# V1_0.net
KiCad netlist of a schematic drawn in Altium Designer
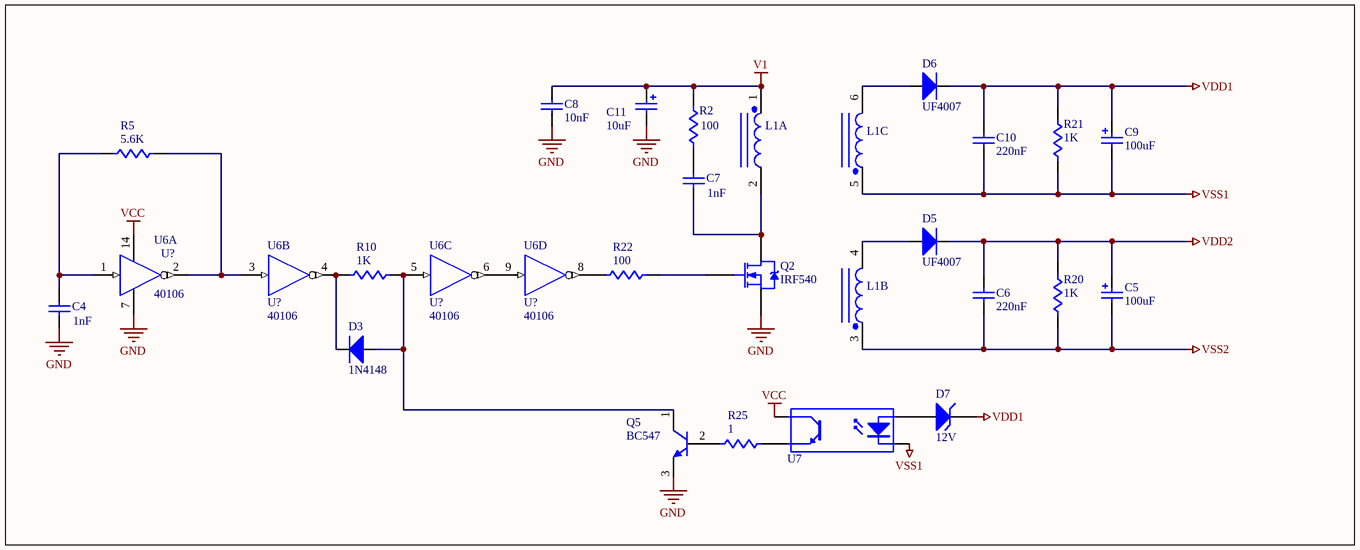
[diagram p0: V1.0.SchDoc]

(export (version "E")
  (design (tool "Eeschema 10.0.6"))
  (components
    (comp (ref "C4")
      (value "1nF")
      (footprint "CAPNTO2.54-3.05x1.78A")
      (description "Capacitor")
      (fields
        (field (name "MANUFACTURER") "Generic Components")
        (field (name "Comment") "Cap")
        (field (name "PUBLISHER") "Altium Limited")
      )
      (libsource (lib "Miscellaneous Devices") (part "Cap"))
    )
    (comp (ref "C5")
      (value "100uF")
      (footprint "CAPPR2.5-6.3x5")
      (description "Polarized Capacitor (Radial)")
      (fields
        (field (name "MANUFACTURER") "Generic Components")
        (field (name "Comment") "Cap Pol1")
        (field (name "PUBLISHER") "Altium Limited")
      )
      (libsource (lib "Miscellaneous Devices") (part "Cap Pol1"))
    )
    (comp (ref "C6")
      (value "220nF")
      (footprint "CAPNTO5.08-7.37x3.94")
      (description "Capacitor")
      (fields
        (field (name "MANUFACTURER") "Generic Components")
        (field (name "Comment") "Cap")
        (field (name "PUBLISHER") "Altium Limited")
      )
      (libsource (lib "Miscellaneous Devices") (part "Cap"))
    )
    (comp (ref "C7")
      (value "1nF")
      (footprint "CAPNTO2.54-3.56x2.03")
      (description "Capacitor")
      (fields
        (field (name "MANUFACTURER") "Generic Components")
        (field (name "Comment") "Cap")
        (field (name "PUBLISHER") "Altium Limited")
      )
      (libsource (lib "Miscellaneous Devices") (part "Cap"))
    )
    (comp (ref "C8")
      (value "10nF")
      (footprint "CAPNTO2.54-3.05x1.78A")
      (description "Capacitor")
      (fields
        (field (name "MANUFACTURER") "Generic Components")
        (field (name "Comment") "Cap")
        (field (name "PUBLISHER") "Altium Limited")
      )
      (libsource (lib "Miscellaneous Devices") (part "Cap"))
    )
    (comp (ref "C9")
      (value "100uF")
      (footprint "CAPPR2.5-6.3x5")
      (description "Polarized Capacitor (Radial)")
      (fields
        (field (name "MANUFACTURER") "Generic Components")
        (field (name "Comment") "Cap Pol1")
        (field (name "PUBLISHER") "Altium Limited")
      )
      (libsource (lib "Miscellaneous Devices") (part "Cap Pol1"))
    )
    (comp (ref "C10")
      (value "220nF")
      (footprint "CAPNTO5.08-7.37x3.94")
      (description "Capacitor")
      (fields
        (field (name "MANUFACTURER") "Generic Components")
        (field (name "Comment") "Cap")
        (field (name "PUBLISHER") "Altium Limited")
      )
      (libsource (lib "Miscellaneous Devices") (part "Cap"))
    )
    (comp (ref "C11")
      (value "10uF")
      (footprint "CAPPR2.5-6.3x5")
      (description "Polarized Capacitor (Radial)")
      (fields
        (field (name "MANUFACTURER") "Generic Components")
        (field (name "Comment") "Cap Pol1")
        (field (name "PUBLISHER") "Altium Limited")
      )
      (libsource (lib "Miscellaneous Devices") (part "Cap Pol1"))
    )
    (comp (ref "D3")
      (value "1N4148")
      (footprint "DIODE0.2_")
      (description "Default Diode")
      (fields (field (name "MANUFACTURER") "Generic Components") (field (name "PUBLISHER") "Altium Limited"))
      (libsource (lib "Miscellaneous Devices") (part "Diode"))
    )
    (comp (ref "D5")
      (value "UF4007")
      (footprint "DIODE-0.4")
      (description "Default Diode")
      (fields (field (name "MANUFACTURER") "Generic Components") (field (name "PUBLISHER") "Altium Limited"))
      (libsource (lib "Miscellaneous Devices") (part "Diode"))
    )
    (comp (ref "D6")
      (value "UF4007")
      (footprint "DIODE-0.4")
      (description "Default Diode")
      (fields (field (name "MANUFACTURER") "Generic Components") (field (name "PUBLISHER") "Altium Limited"))
      (libsource (lib "Miscellaneous Devices") (part "Diode"))
    )
    (comp (ref "D7")
      (value "12V")
      (footprint "DIODE-0.4")
      (description "Zener Diode")
      (fields
        (field (name "MANUFACTURER") "Generic Components")
        (field (name "Comment") "D Zener")
        (field (name "PUBLISHER") "Altium Limited")
      )
      (libsource (lib "Miscellaneous Devices") (part "D Zener"))
    )
    (comp (ref "L1")
      (value "Inductor 2*3")
      (footprint "INDUCTOR3")
      (fields (field (name "PUBLISHER") "Altium Limited"))
      (libsource (lib "") (part "Inductor 2*3_1"))
    )
    (comp (ref "Q2")
      (value "IRF540")
      (footprint "TO220V")
      (description "31A, 80V, 0.077 Ohm, N-Channel Power MOSFET")
      (fields (field (name "PUBLISHER") "Altium Limited"))
      (libsource (lib "Intersil Discrete MOSFET") (part "IRFP141"))
    )
    (comp (ref "Q5")
      (value "BC547")
      (footprint "TO92C")
      (description "NPN Bipolar Transistor")
      (fields
        (field (name "MANUFACTURER") "Generic Components")
        (field (name "Comment") "NPN")
        (field (name "PUBLISHER") "Altium Limited")
      )
      (libsource (lib "Miscellaneous Devices") (part "NPN"))
    )
    (comp (ref "R2")
      (value "100")
      (footprint "HDR1X2")
      (description "Resistor")
      (fields
        (field (name "MANUFACTURER") "Generic Components")
        (field (name "Comment") "Res1")
        (field (name "PUBLISHER") "Altium Limited")
      )
      (libsource (lib "Miscellaneous Devices") (part "Res1"))
    )
    (comp (ref "R5")
      (value "5.6K")
      (footprint "HDR1X2")
      (description "Resistor")
      (fields
        (field (name "MANUFACTURER") "Generic Components")
        (field (name "Comment") "Res1")
        (field (name "PUBLISHER") "Altium Limited")
      )
      (libsource (lib "Miscellaneous Devices") (part "Res1"))
    )
    (comp (ref "R10")
      (value "1K")
      (footprint "HDR1X2")
      (description "Resistor")
      (fields
        (field (name "MANUFACTURER") "Generic Components")
        (field (name "Comment") "Res1")
        (field (name "PUBLISHER") "Altium Limited")
      )
      (libsource (lib "Miscellaneous Devices") (part "Res1"))
    )
    (comp (ref "R20")
      (value "1K")
      (footprint "HDR1X2")
      (description "Resistor")
      (fields
        (field (name "MANUFACTURER") "Generic Components")
        (field (name "Comment") "Res1")
        (field (name "PUBLISHER") "Altium Limited")
      )
      (libsource (lib "Miscellaneous Devices") (part "Res1"))
    )
    (comp (ref "R21")
      (value "1K")
      (footprint "HDR1X2")
      (description "Resistor")
      (fields
        (field (name "MANUFACTURER") "Generic Components")
        (field (name "Comment") "Res1")
        (field (name "PUBLISHER") "Altium Limited")
      )
      (libsource (lib "Miscellaneous Devices") (part "Res1"))
    )
    (comp (ref "R22")
      (value "100")
      (footprint "HDR1X2")
      (description "Resistor")
      (fields
        (field (name "MANUFACTURER") "Generic Components")
        (field (name "Comment") "Res1")
        (field (name "PUBLISHER") "Altium Limited")
      )
      (libsource (lib "Miscellaneous Devices") (part "Res1"))
    )
    (comp (ref "R25")
      (value "1")
      (footprint "AXIAL-0.4")
      (description "Resistor")
      (fields
        (field (name "MANUFACTURER") "Generic Components")
        (field (name "Comment") "Res1")
        (field (name "PUBLISHER") "Altium Limited")
      )
      (libsource (lib "Miscellaneous Devices") (part "Res1"))
    )
    (comp (ref "U6")
      (value "U?")
      (footprint "DIP14")
      (description "Hex inverting Schmitt trigger, 14-Pin")
      (fields (field (name "ALTIUM_VALUE") "40106") (field (name "PUBLISHER") "Altium Limited"))
      (libsource (lib "my Libraries") (part "40106"))
    )
    (comp (ref "U7")
      (value "Optoisolator1")
      (footprint "DIP-4")
      (description "4-Pin Phototransistor Optocoupler")
      (fields (field (name "PUBLISHER") "Altium Limited"))
      (libsource (lib "Miscellaneous Devices") (part "Optoisolator1"))
    )
  )
  (nets
    (net (code "1") (name "GND") (class "Default")
      (node (ref "C11") (pin "2") (pinfunction "2_2") (pintype "passive"))
      (node (ref "C4") (pin "1") (pinfunction "1_1") (pintype "passive"))
      (node (ref "C8") (pin "1") (pinfunction "1_1") (pintype "passive"))
      (node (ref "Q2") (pin "3") (pinfunction "S_3") (pintype "passive"))
      (node (ref "Q5") (pin "3") (pinfunction "E_3") (pintype "passive"))
      (node (ref "U6") (pin "7") (pinfunction "VSS_7") (pintype "power_in"))
    )
    (net (code "2") (name "Net-(C7-Pad2)") (class "Default")
      (node (ref "C7") (pin "2") (pinfunction "2_2") (pintype "passive"))
      (node (ref "R2") (pin "2") (pinfunction "2_2") (pintype "passive"))
    )
    (net (code "3") (name "Net-(D3-A)") (class "Default")
      (node (ref "D3") (pin "1") (pinfunction "A_1") (pintype "passive"))
      (node (ref "Q5") (pin "1") (pinfunction "C_1") (pintype "passive"))
      (node (ref "R10") (pin "1") (pinfunction "1_1") (pintype "passive"))
      (node (ref "U6") (pin "5") (pinfunction "I_5") (pintype "input"))
    )
    (net (code "4") (name "Net-(D3-K)") (class "Default")
      (node (ref "D3") (pin "2") (pinfunction "K_2") (pintype "passive"))
      (node (ref "R10") (pin "2") (pinfunction "2_2") (pintype "passive"))
      (node (ref "U6") (pin "4") (pinfunction "~{O}_4") (pintype "output"))
    )
    (net (code "5") (name "Net-(D5-A)") (class "Default")
      (node (ref "D5") (pin "1") (pinfunction "A_1") (pintype "passive"))
      (node (ref "L1") (pin "4") (pinfunction "4_4") (pintype "passive"))
    )
    (net (code "6") (name "Net-(D6-A)") (class "Default")
      (node (ref "D6") (pin "1") (pinfunction "A_1") (pintype "passive"))
      (node (ref "L1") (pin "6") (pinfunction "6_6") (pintype "passive"))
    )
    (net (code "7") (name "Net-(D7-A)") (class "Default")
      (node (ref "D7") (pin "1") (pinfunction "A_1") (pintype "passive"))
      (node (ref "U7") (pin "1") (pinfunction "A_1") (pintype "passive"))
    )
    (net (code "8") (name "Net-(Q2-D)") (class "Default")
      (node (ref "C7") (pin "1") (pinfunction "1_1") (pintype "passive"))
      (node (ref "L1") (pin "2") (pinfunction "2_2") (pintype "passive"))
      (node (ref "Q2") (pin "2") (pinfunction "D_2") (pintype "passive"))
    )
    (net (code "9") (name "Net-(Q2-G)") (class "Default")
      (node (ref "Q2") (pin "1") (pinfunction "G_1") (pintype "passive"))
      (node (ref "R22") (pin "2") (pinfunction "2_2") (pintype "passive"))
    )
    (net (code "10") (name "Net-(Q5-B)") (class "Default")
      (node (ref "Q5") (pin "2") (pinfunction "B_2") (pintype "passive"))
      (node (ref "R25") (pin "1") (pinfunction "1_1") (pintype "passive"))
    )
    (net (code "11") (name "Net-(U6A-I)") (class "Default")
      (node (ref "C4") (pin "2") (pinfunction "2_2") (pintype "passive"))
      (node (ref "R5") (pin "2") (pinfunction "2_2") (pintype "passive"))
      (node (ref "U6") (pin "1") (pinfunction "I_1") (pintype "input"))
    )
    (net (code "12") (name "Net-(U6A-~{O})") (class "Default")
      (node (ref "R5") (pin "1") (pinfunction "1_1") (pintype "passive"))
      (node (ref "U6") (pin "2") (pinfunction "~{O}_2") (pintype "output"))
      (node (ref "U6") (pin "3") (pinfunction "I_3") (pintype "input"))
    )
    (net (code "13") (name "Net-(U6C-~{O})") (class "Default")
      (node (ref "U6") (pin "6") (pinfunction "~{O}_6") (pintype "output"))
      (node (ref "U6") (pin "9") (pinfunction "I_9") (pintype "input"))
    )
    (net (code "14") (name "Net-(U6D-~{O})") (class "Default")
      (node (ref "R22") (pin "1") (pinfunction "1_1") (pintype "passive"))
      (node (ref "U6") (pin "8") (pinfunction "~{O}_8") (pintype "output"))
    )
    (net (code "15") (name "Net-(U7-E)") (class "Default")
      (node (ref "R25") (pin "2") (pinfunction "2_2") (pintype "passive"))
      (node (ref "U7") (pin "3") (pinfunction "E_3") (pintype "passive"))
    )
    (net (code "16") (name "V1") (class "Default")
      (node (ref "C11") (pin "1") (pinfunction "1_1") (pintype "passive"))
      (node (ref "C8") (pin "2") (pinfunction "2_2") (pintype "passive"))
      (node (ref "L1") (pin "1") (pinfunction "1_1") (pintype "passive"))
      (node (ref "R2") (pin "1") (pinfunction "1_1") (pintype "passive"))
    )
    (net (code "17") (name "VCC") (class "Default")
      (node (ref "U6") (pin "14") (pinfunction "VDD_14") (pintype "passive"))
      (node (ref "U7") (pin "4") (pinfunction "C_4") (pintype "passive"))
    )
    (net (code "18") (name "VDD1") (class "Default")
      (node (ref "C10") (pin "2") (pinfunction "2_2") (pintype "passive"))
      (node (ref "C9") (pin "1") (pinfunction "1_1") (pintype "passive"))
      (node (ref "D6") (pin "2") (pinfunction "K_2") (pintype "passive"))
      (node (ref "D7") (pin "2") (pinfunction "K_2") (pintype "passive"))
      (node (ref "R21") (pin "1") (pinfunction "1_1") (pintype "passive"))
    )
    (net (code "19") (name "VDD2") (class "Default")
      (node (ref "C5") (pin "1") (pinfunction "1_1") (pintype "passive"))
      (node (ref "C6") (pin "2") (pinfunction "2_2") (pintype "passive"))
      (node (ref "D5") (pin "2") (pinfunction "K_2") (pintype "passive"))
      (node (ref "R20") (pin "1") (pinfunction "1_1") (pintype "passive"))
    )
    (net (code "20") (name "VSS1") (class "Default")
      (node (ref "C10") (pin "1") (pinfunction "1_1") (pintype "passive"))
      (node (ref "C9") (pin "2") (pinfunction "2_2") (pintype "passive"))
      (node (ref "L1") (pin "5") (pinfunction "5_5") (pintype "passive"))
      (node (ref "R21") (pin "2") (pinfunction "2_2") (pintype "passive"))
      (node (ref "U7") (pin "2") (pinfunction "K_2") (pintype "passive"))
    )
    (net (code "21") (name "VSS2") (class "Default")
      (node (ref "C5") (pin "2") (pinfunction "2_2") (pintype "passive"))
      (node (ref "C6") (pin "1") (pinfunction "1_1") (pintype "passive"))
      (node (ref "L1") (pin "3") (pinfunction "3_3") (pintype "passive"))
      (node (ref "R20") (pin "2") (pinfunction "2_2") (pintype "passive"))
    )
  )
)
